# 4draft_offBoard.net
KiCad netlist of a schematic drawn in EAGLE
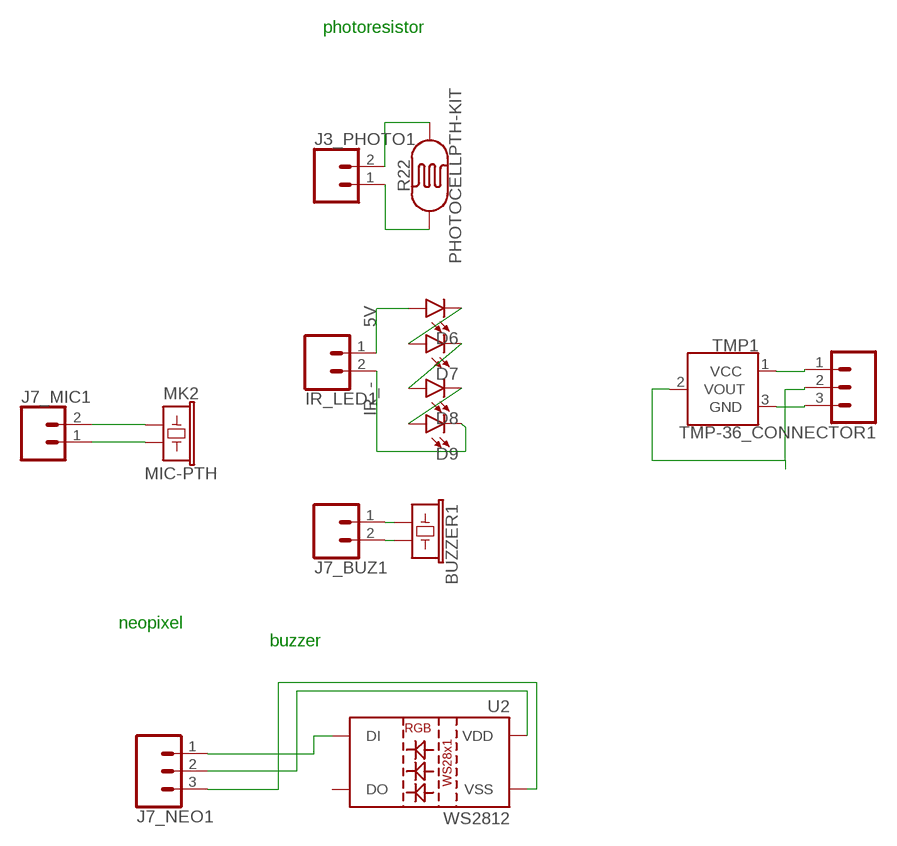
[diagram p0: schematic, sheet 1]

(export (version "E")
  (design (tool "Eeschema 10.0.6"))
  (components
    (comp (ref "BUZZER1")
      (value "BUZZER-PTH")
      (footprint "eagle-import:BUZZER-12MM")
      (libsource (lib "eagle-import") (part "BUZZER-PTH"))
    )
    (comp (ref "D6")
      (value "LED-IRTSAL6100")
      (footprint "eagle-import:LED_5MM")
      (libsource (lib "eagle-import") (part "LED-IRTSAL6100"))
    )
    (comp (ref "D7")
      (value "LED-IRTSAL6100")
      (footprint "eagle-import:LED_5MM")
      (libsource (lib "eagle-import") (part "LED-IRTSAL6100"))
    )
    (comp (ref "D8")
      (value "LED-IRTSAL6100")
      (footprint "eagle-import:LED_5MM")
      (libsource (lib "eagle-import") (part "LED-IRTSAL6100"))
    )
    (comp (ref "D9")
      (value "LED-IRTSAL6100")
      (footprint "eagle-import:LED_5MM")
      (libsource (lib "eagle-import") (part "LED-IRTSAL6100"))
    )
    (comp (ref "IR_LED1")
      (value "CONN_02LOCK")
      (footprint "eagle-import:1X02_LOCK")
      (libsource (lib "eagle-import") (part "CONN_02LOCK"))
    )
    (comp (ref "J3_PHOTO1")
      (value "CONN_02LOCK")
      (footprint "eagle-import:1X02_LOCK")
      (libsource (lib "eagle-import") (part "CONN_02LOCK"))
    )
    (comp (ref "J7_BUZ1")
      (value "CONN_02LOCK")
      (footprint "eagle-import:1X02_LOCK")
      (libsource (lib "eagle-import") (part "CONN_02LOCK"))
    )
    (comp (ref "J7_MIC1")
      (value "CONN_02LOCK")
      (footprint "eagle-import:1X02_LOCK")
      (libsource (lib "eagle-import") (part "CONN_02LOCK"))
    )
    (comp (ref "J7_NEO1")
      (value "CONN_03")
      (footprint "eagle-import:1X03")
      (libsource (lib "eagle-import") (part "CONN_03"))
    )
    (comp (ref "MK2")
      (value "MIC-PTH")
      (footprint "eagle-import:MICROPHONE-PTH-9.7MM")
      (libsource (lib "eagle-import") (part "MIC-PTH"))
    )
    (comp (ref "R22")
      (value "PHOTOCELLPTH-KIT")
      (footprint "eagle-import:PHOTOCELL-KIT")
      (libsource (lib "eagle-import") (part "PHOTOCELLPTH-KIT"))
    )
    (comp (ref "TMP-36_CONNECTOR1")
      (value "CONN_03")
      (footprint "eagle-import:1X03")
      (libsource (lib "eagle-import") (part "CONN_03"))
    )
    (comp (ref "TMP1")
      (value "TMP36GT9")
      (footprint "eagle-import:TO-92")
      (libsource (lib "eagle-import") (part "TMP36GT9"))
    )
    (comp (ref "U2")
      (value "WS2812")
      (footprint "eagle-import:LED-TRICOLOR-5050-IC")
      (libsource (lib "eagle-import") (part "WS2812{dblquote}"))
    )
  )
  (nets
    (net (code "1") (name "/5V") (class "Default")
      (node (ref "D6") (pin "A") (pinfunction "A_A") (pintype "passive"))
      (node (ref "IR_LED1") (pin "1") (pinfunction "1_1") (pintype "passive"))
    )
    (net (code "2") (name "/IR_-") (class "Default")
      (node (ref "D9") (pin "K") (pinfunction "C_K") (pintype "passive"))
      (node (ref "IR_LED1") (pin "2") (pinfunction "2_2") (pintype "passive"))
    )
    (net (code "3") (name "Net-(BUZZER1-1)") (class "Default")
      (node (ref "BUZZER1") (pin "+") (pinfunction "1_+") (pintype "passive"))
      (node (ref "J7_BUZ1") (pin "1") (pinfunction "1_1") (pintype "passive"))
    )
    (net (code "4") (name "Net-(BUZZER1-2)") (class "Default")
      (node (ref "BUZZER1") (pin "-") (pinfunction "2_-") (pintype "passive"))
      (node (ref "J7_BUZ1") (pin "2") (pinfunction "2_2") (pintype "passive"))
    )
    (net (code "5") (name "Net-(D6-C)") (class "Default")
      (node (ref "D6") (pin "K") (pinfunction "C_K") (pintype "passive"))
      (node (ref "D7") (pin "A") (pinfunction "A_A") (pintype "passive"))
    )
    (net (code "6") (name "Net-(D7-C)") (class "Default")
      (node (ref "D7") (pin "K") (pinfunction "C_K") (pintype "passive"))
      (node (ref "D8") (pin "A") (pinfunction "A_A") (pintype "passive"))
    )
    (net (code "7") (name "Net-(D8-C)") (class "Default")
      (node (ref "D8") (pin "K") (pinfunction "C_K") (pintype "passive"))
      (node (ref "D9") (pin "A") (pinfunction "A_A") (pintype "passive"))
    )
    (net (code "8") (name "Net-(J7_NEO1-Pad2)") (class "Default")
      (node (ref "J7_NEO1") (pin "2") (pinfunction "2_2") (pintype "passive"))
      (node (ref "U2") (pin "3") (pinfunction "VDD_3") (pintype "bidirectional"))
      (node (ref "U2") (pin "5") (pinfunction "VDD_5") (pintype "bidirectional"))
    )
    (net (code "9") (name "Net-(MK2-1)") (class "Default")
      (node (ref "J7_MIC1") (pin "2") (pinfunction "2_2") (pintype "passive"))
      (node (ref "MK2") (pin "OUT") (pinfunction "1_OUT") (pintype "passive"))
    )
    (net (code "10") (name "Net-(MK2-2)") (class "Default")
      (node (ref "J7_MIC1") (pin "1") (pinfunction "1_1") (pintype "passive"))
      (node (ref "MK2") (pin "GND") (pinfunction "2_GND") (pintype "passive"))
    )
    (net (code "11") (name "Net-(R22-P$1)") (class "Default")
      (node (ref "J3_PHOTO1") (pin "1") (pinfunction "1_1") (pintype "passive"))
      (node (ref "R22") (pin "1") (pinfunction "P$1_1") (pintype "bidirectional"))
    )
    (net (code "12") (name "Net-(R22-P$2)") (class "Default")
      (node (ref "J3_PHOTO1") (pin "2") (pinfunction "2_2") (pintype "passive"))
      (node (ref "R22") (pin "2") (pinfunction "P$2_2") (pintype "bidirectional"))
    )
    (net (code "13") (name "Net-(TMP1-GND)") (class "Default")
      (node (ref "TMP-36_CONNECTOR1") (pin "3") (pinfunction "3_3") (pintype "passive"))
      (node (ref "TMP1") (pin "3") (pinfunction "GND_3") (pintype "bidirectional"))
    )
    (net (code "14") (name "Net-(TMP1-VCC)") (class "Default")
      (node (ref "TMP-36_CONNECTOR1") (pin "1") (pinfunction "1_1") (pintype "passive"))
      (node (ref "TMP1") (pin "1") (pinfunction "VCC_1") (pintype "bidirectional"))
    )
    (net (code "15") (name "Net-(TMP1-VOUT)") (class "Default")
      (node (ref "TMP-36_CONNECTOR1") (pin "2") (pinfunction "2_2") (pintype "passive"))
      (node (ref "TMP1") (pin "2") (pinfunction "VOUT_2") (pintype "bidirectional"))
    )
    (net (code "16") (name "Net-(U2-DI)") (class "Default")
      (node (ref "J7_NEO1") (pin "1") (pinfunction "1_1") (pintype "passive"))
      (node (ref "U2") (pin "2") (pinfunction "DI_2") (pintype "bidirectional"))
    )
    (net (code "17") (name "Net-(U2-VSS)") (class "Default")
      (node (ref "J7_NEO1") (pin "3") (pinfunction "3_3") (pintype "passive"))
      (node (ref "U2") (pin "6") (pinfunction "VSS_6") (pintype "bidirectional"))
    )
    (net (code "18") (name "unconnected-(U2-DO-Pad1)") (class "Default")
      (node (ref "U2") (pin "1") (pinfunction "DO_1") (pintype "bidirectional"))
    )
  )
)
